# Spring2020.net
KiCad netlist of a schematic drawn in EAGLE
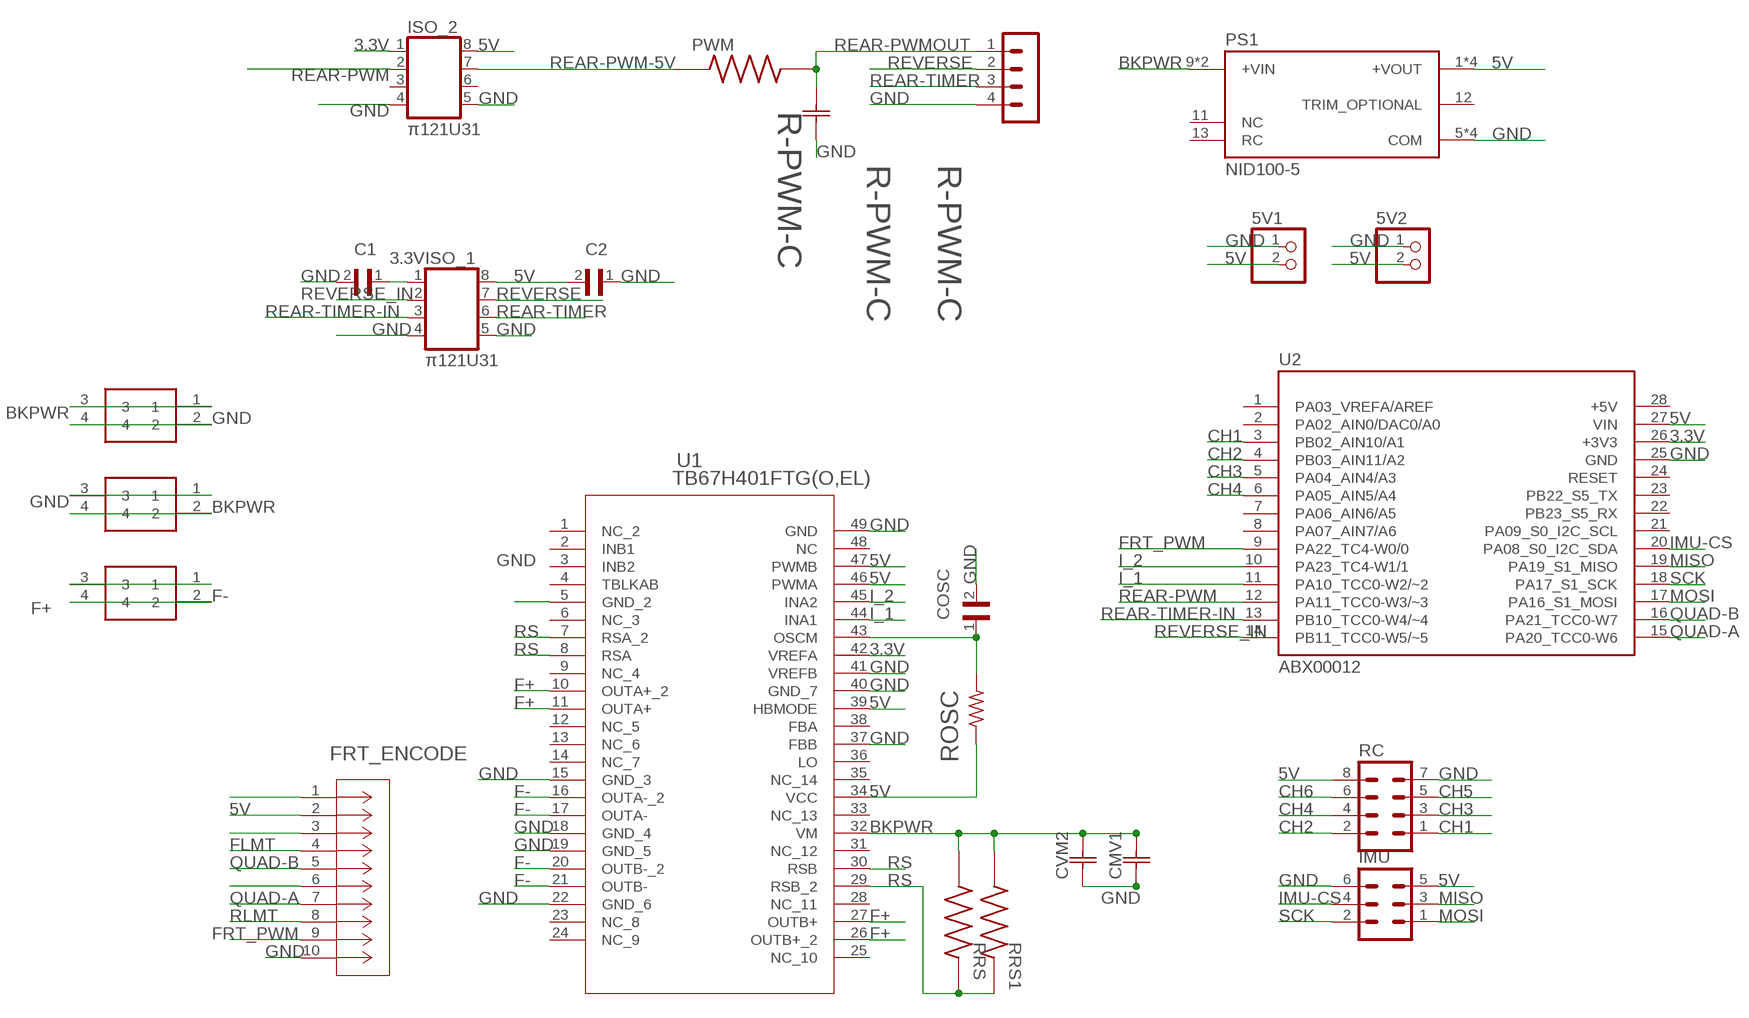
[diagram p0: schematic, sheet 1]

(export (version "E")
  (design (tool "Eeschema 10.0.6"))
  (components
    (comp (ref "5V1")
      (value "PINHD-1X2")
      (footprint "eagle-import:1X02")
      (libsource (lib "eagle-import") (part "PINHD-1X2"))
    )
    (comp (ref "5V2")
      (value "PINHD-1X2")
      (footprint "eagle-import:1X02")
      (libsource (lib "eagle-import") (part "PINHD-1X2"))
    )
    (comp (ref "C1")
      (value "CL05A105KP5NNNC")
      (footprint "eagle-import:CAPC1005X55N")
      (libsource (lib "eagle-import") (part "CL05A105KP5NNNC"))
    )
    (comp (ref "C2")
      (value "CL05A105KP5NNNC")
      (footprint "eagle-import:CAPC1005X55N")
      (libsource (lib "eagle-import") (part "CL05A105KP5NNNC"))
    )
    (comp (ref "CMV1")
      (value "UVY1H102MHD")
      (footprint "eagle-import:CAP_12.5_X_25_NCH")
      (fields (field (name "COPYRIGHT") "Copyright (C) 2022 Ultra Librarian. All rights reserved."))
      (libsource (lib "eagle-import") (part "UVY1H102MHD"))
    )
    (comp (ref "COSC")
      (value "GRM022R71A271KA01L")
      (footprint "eagle-import:CAPC0402X22N")
      (libsource (lib "eagle-import") (part "GRM022R71A271KA01L"))
    )
    (comp (ref "CVM2")
      (value "CL05B104KB54PNC")
      (footprint "eagle-import:CAP_CL_05_SAM")
      (fields (field (name "COPYRIGHT") "Copyright (C) 2022 Ultra Librarian. All rights reserved."))
      (libsource (lib "eagle-import") (part "CL05B104KB54PNC"))
    )
    (comp (ref "FRT_ENCODE")
      (value "3220-10-0100-00")
      (footprint "eagle-import:CONN_3220-10-0100-00_CNC")
      (fields (field (name "COPYRIGHT") "Copyright (C) 2022 Ultra Librarian. All rights reserved."))
      (libsource (lib "eagle-import") (part "3220-10-0100-00"))
    )
    (comp (ref "FRT_MTR")
      (value "2060-452_998-404")
      (footprint "eagle-import:2060452998404")
      (fields (field (name "MANUFACTURER_PART_NUMBER") "2060-452/998-404"))
      (libsource (lib "eagle-import") (part "2060-452_998-404"))
    )
    (comp (ref "IMU")
      (value "MA03-2")
      (footprint "eagle-import:MA03-2")
      (libsource (lib "eagle-import") (part "MA03-2"))
    )
    (comp (ref "ISO_1")
      (value "π121U31")
      (footprint "eagle-import:SO08")
      (libsource (lib "eagle-import") (part "π121U31"))
    )
    (comp (ref "ISO_2")
      (value "π121U31")
      (footprint "eagle-import:SO08")
      (libsource (lib "eagle-import") (part "π121U31"))
    )
    (comp (ref "PS1")
      (value "NID100-5")
      (footprint "eagle-import:CONV_NID100-5")
      (fields (field (name "MANUFACTURER") "Meanwell"))
      (libsource (lib "eagle-import") (part "NID100-5"))
    )
    (comp (ref "PWM")
      (value "ERJ1GNF6802C")
      (footprint "eagle-import:RES_ERJ1GNF6802C")
      (fields (field (name "MANUFACTURER") "Panasonic"))
      (libsource (lib "eagle-import") (part "ERJ1GNF6802C"))
    )
    (comp (ref "PWR_IN")
      (value "2060-452_998-404")
      (footprint "eagle-import:2060452998404")
      (fields (field (name "MANUFACTURER_PART_NUMBER") "2060-452/998-404"))
      (libsource (lib "eagle-import") (part "2060-452_998-404"))
    )
    (comp (ref "R-PWM-C")
      (value "CL03A105MQ3CSNC")
      (footprint "eagle-import:CAP_CL03_SAM")
      (fields (field (name "COPYRIGHT") "Copyright (C) 2022 Ultra Librarian. All rights reserved."))
      (libsource (lib "eagle-import") (part "CL03A105MQ3CSNC"))
    )
    (comp (ref "RC")
      (value "MA04-2")
      (footprint "eagle-import:MA04-2")
      (libsource (lib "eagle-import") (part "MA04-2"))
    )
    (comp (ref "REAR-MOTOR")
      (value "MA04-1")
      (footprint "eagle-import:MA04-1")
      (libsource (lib "eagle-import") (part "MA04-1"))
    )
    (comp (ref "REAR_PWR")
      (value "2060-452_998-404")
      (footprint "eagle-import:2060452998404")
      (fields (field (name "MANUFACTURER_PART_NUMBER") "2060-452/998-404"))
      (libsource (lib "eagle-import") (part "2060-452_998-404"))
    )
    (comp (ref "ROSC")
      (value "R-US_R0402")
      (footprint "eagle-import:R0402")
      (libsource (lib "eagle-import") (part "R-US_R0402"))
    )
    (comp (ref "RRS")
      (value "RLP73K3AR22FTDF")
      (footprint "eagle-import:RESC6331X70N")
      (libsource (lib "eagle-import") (part "RLP73K3AR22FTDF"))
    )
    (comp (ref "RRS1")
      (value "RLP73K3AR22FTDF")
      (footprint "eagle-import:RESC6331X70N")
      (libsource (lib "eagle-import") (part "RLP73K3AR22FTDF"))
    )
    (comp (ref "U1")
      (value "TB67H401FTG(O,EL)")
      (footprint "eagle-import:P-VQFN48-0707-0P50-004_TOS")
      (fields (field (name "COPYRIGHT") "Copyright (C) 2022 Ultra Librarian. All rights reserved."))
      (libsource (lib "eagle-import") (part "TB67H401FTG(O,EL)"))
    )
    (comp (ref "U2")
      (value "ABX00012")
      (footprint "eagle-import:ARDUINO_ABX00012")
      (fields (field (name "MANUFACTURER") "Arduino"))
      (libsource (lib "eagle-import") (part "ABX00012"))
    )
  )
  (nets
    (net (code "1") (name "/+5V") (class "Default")
      (node (ref "U2") (pin "28") (pinfunction "+5V_28") (pintype "power_in"))
    )
    (net (code "2") (name "/3.3V") (class "Default")
      (node (ref "C1") (pin "1") (pinfunction "1_1") (pintype "passive"))
      (node (ref "ISO_1") (pin "1") (pinfunction "1_1") (pintype "passive"))
      (node (ref "ISO_2") (pin "1") (pinfunction "1_1") (pintype "passive"))
      (node (ref "U1") (pin "42") (pinfunction "VREFA_42") (pintype "power_in"))
      (node (ref "U2") (pin "26") (pinfunction "+3V3_26") (pintype "power_in"))
    )
    (net (code "3") (name "/5V") (class "Default")
      (node (ref "5V1") (pin "2") (pinfunction "2_2") (pintype "passive"))
      (node (ref "5V2") (pin "2") (pinfunction "2_2") (pintype "passive"))
      (node (ref "C2") (pin "2") (pinfunction "2_2") (pintype "passive"))
      (node (ref "FRT_ENCODE") (pin "2") (pinfunction "2_2") (pintype "passive"))
      (node (ref "IMU") (pin "5") (pinfunction "5_5") (pintype "passive"))
      (node (ref "ISO_1") (pin "8") (pinfunction "8_8") (pintype "passive"))
      (node (ref "ISO_2") (pin "8") (pinfunction "8_8") (pintype "passive"))
      (node (ref "PS1") (pin "1") (pinfunction "+VOUT_1") (pintype "output"))
      (node (ref "PS1") (pin "2") (pinfunction "+VOUT_2") (pintype "output"))
      (node (ref "PS1") (pin "3") (pinfunction "+VOUT_3") (pintype "output"))
      (node (ref "PS1") (pin "4") (pinfunction "+VOUT_4") (pintype "output"))
      (node (ref "RC") (pin "8") (pinfunction "8_8") (pintype "passive"))
      (node (ref "ROSC") (pin "1") (pinfunction "1_1") (pintype "passive"))
      (node (ref "U1") (pin "34") (pinfunction "VCC_34") (pintype "power_in"))
      (node (ref "U1") (pin "39") (pinfunction "HBMODE_39") (pintype "passive"))
      (node (ref "U1") (pin "46") (pinfunction "PWMA_46") (pintype "passive"))
      (node (ref "U1") (pin "47") (pinfunction "PWMB_47") (pintype "passive"))
      (node (ref "U2") (pin "27") (pinfunction "VIN_27") (pintype "power_in"))
    )
    (net (code "4") (name "/BKPWR") (class "Default")
      (node (ref "CMV1") (pin "2") (pinfunction "2_2") (pintype "passive"))
      (node (ref "CVM2") (pin "2") (pinfunction "2_2") (pintype "passive"))
      (node (ref "PS1") (pin "10") (pinfunction "+VIN_10") (pintype "input"))
      (node (ref "PS1") (pin "9") (pinfunction "+VIN_9") (pintype "input"))
      (node (ref "PWR_IN") (pin "1") (pinfunction "1_1") (pintype "bidirectional"))
      (node (ref "PWR_IN") (pin "3") (pinfunction "3_3") (pintype "bidirectional"))
      (node (ref "REAR_PWR") (pin "2") (pinfunction "2_2") (pintype "bidirectional"))
      (node (ref "REAR_PWR") (pin "4") (pinfunction "4_4") (pintype "bidirectional"))
      (node (ref "RRS") (pin "1") (pinfunction "1_1") (pintype "passive"))
      (node (ref "RRS1") (pin "1") (pinfunction "1_1") (pintype "passive"))
      (node (ref "U1") (pin "32") (pinfunction "VM_32") (pintype "passive"))
    )
    (net (code "5") (name "/CH1") (class "Default")
      (node (ref "RC") (pin "1") (pinfunction "1_1") (pintype "passive"))
      (node (ref "U2") (pin "3") (pinfunction "PB02_AIN10/A1_3") (pintype "bidirectional"))
    )
    (net (code "6") (name "/CH2") (class "Default")
      (node (ref "RC") (pin "2") (pinfunction "2_2") (pintype "passive"))
      (node (ref "U2") (pin "4") (pinfunction "PB03_AIN11/A2_4") (pintype "bidirectional"))
    )
    (net (code "7") (name "/CH3") (class "Default")
      (node (ref "RC") (pin "3") (pinfunction "3_3") (pintype "passive"))
      (node (ref "U2") (pin "5") (pinfunction "PA04_AIN4/A3_5") (pintype "bidirectional"))
    )
    (net (code "8") (name "/CH4") (class "Default")
      (node (ref "RC") (pin "4") (pinfunction "4_4") (pintype "passive"))
      (node (ref "U2") (pin "6") (pinfunction "PA05_AIN5/A4_6") (pintype "bidirectional"))
    )
    (net (code "9") (name "/CH5") (class "Default")
      (node (ref "RC") (pin "5") (pinfunction "5_5") (pintype "passive"))
    )
    (net (code "10") (name "/CH6") (class "Default")
      (node (ref "RC") (pin "6") (pinfunction "6_6") (pintype "passive"))
    )
    (net (code "11") (name "/F+") (class "Default")
      (node (ref "FRT_MTR") (pin "2") (pinfunction "2_2") (pintype "bidirectional"))
      (node (ref "FRT_MTR") (pin "4") (pinfunction "4_4") (pintype "bidirectional"))
      (node (ref "U1") (pin "10") (pinfunction "OUTA+_2_10") (pintype "output"))
      (node (ref "U1") (pin "11") (pinfunction "OUTA+_11") (pintype "output"))
      (node (ref "U1") (pin "26") (pinfunction "OUTB+_2_26") (pintype "output"))
      (node (ref "U1") (pin "27") (pinfunction "OUTB+_27") (pintype "output"))
    )
    (net (code "12") (name "/F-") (class "Default")
      (node (ref "FRT_MTR") (pin "1") (pinfunction "1_1") (pintype "bidirectional"))
      (node (ref "FRT_MTR") (pin "3") (pinfunction "3_3") (pintype "bidirectional"))
      (node (ref "U1") (pin "16") (pinfunction "OUTA-_2_16") (pintype "output"))
      (node (ref "U1") (pin "17") (pinfunction "OUTA-_17") (pintype "output"))
      (node (ref "U1") (pin "20") (pinfunction "OUTB-_2_20") (pintype "output"))
      (node (ref "U1") (pin "21") (pinfunction "OUTB-_21") (pintype "output"))
    )
    (net (code "13") (name "/FLMT") (class "Default")
      (node (ref "FRT_ENCODE") (pin "4") (pinfunction "4_4") (pintype "passive"))
    )
    (net (code "14") (name "/FRT_PWM") (class "Default")
      (node (ref "FRT_ENCODE") (pin "9") (pinfunction "9_9") (pintype "passive"))
      (node (ref "U2") (pin "9") (pinfunction "PA22_TC4-W0/0_9") (pintype "bidirectional"))
    )
    (net (code "15") (name "/GND") (class "Default")
      (node (ref "5V1") (pin "1") (pinfunction "1_1") (pintype "passive"))
      (node (ref "5V2") (pin "1") (pinfunction "1_1") (pintype "passive"))
      (node (ref "C1") (pin "2") (pinfunction "2_2") (pintype "passive"))
      (node (ref "C2") (pin "1") (pinfunction "1_1") (pintype "passive"))
      (node (ref "CMV1") (pin "1") (pinfunction "1_1") (pintype "passive"))
      (node (ref "COSC") (pin "2") (pinfunction "2_2") (pintype "passive"))
      (node (ref "CVM2") (pin "1") (pinfunction "1_1") (pintype "passive"))
      (node (ref "FRT_ENCODE") (pin "10") (pinfunction "10_10") (pintype "passive"))
      (node (ref "IMU") (pin "6") (pinfunction "6_6") (pintype "passive"))
      (node (ref "ISO_1") (pin "4") (pinfunction "4_4") (pintype "passive"))
      (node (ref "ISO_1") (pin "5") (pinfunction "5_5") (pintype "passive"))
      (node (ref "ISO_2") (pin "4") (pinfunction "4_4") (pintype "passive"))
      (node (ref "ISO_2") (pin "5") (pinfunction "5_5") (pintype "passive"))
      (node (ref "PS1") (pin "5") (pinfunction "COM_5") (pintype "passive"))
      (node (ref "PS1") (pin "6") (pinfunction "COM_6") (pintype "passive"))
      (node (ref "PS1") (pin "7") (pinfunction "COM_7") (pintype "passive"))
      (node (ref "PS1") (pin "8") (pinfunction "COM_8") (pintype "passive"))
      (node (ref "PWR_IN") (pin "2") (pinfunction "2_2") (pintype "bidirectional"))
      (node (ref "PWR_IN") (pin "4") (pinfunction "4_4") (pintype "bidirectional"))
      (node (ref "R-PWM-C") (pin "2") (pinfunction "2_2") (pintype "passive"))
      (node (ref "RC") (pin "7") (pinfunction "7_7") (pintype "passive"))
      (node (ref "REAR-MOTOR") (pin "4") (pinfunction "4_4") (pintype "passive"))
      (node (ref "REAR_PWR") (pin "1") (pinfunction "1_1") (pintype "bidirectional"))
      (node (ref "REAR_PWR") (pin "3") (pinfunction "3_3") (pintype "bidirectional"))
      (node (ref "U1") (pin "15") (pinfunction "GND_3_15") (pintype "passive"))
      (node (ref "U1") (pin "18") (pinfunction "GND_4_18") (pintype "passive"))
      (node (ref "U1") (pin "19") (pinfunction "GND_5_19") (pintype "passive"))
      (node (ref "U1") (pin "22") (pinfunction "GND_6_22") (pintype "passive"))
      (node (ref "U1") (pin "37") (pinfunction "FBB_37") (pintype "passive"))
      (node (ref "U1") (pin "40") (pinfunction "GND_7_40") (pintype "passive"))
      (node (ref "U1") (pin "41") (pinfunction "VREFB_41") (pintype "power_in"))
      (node (ref "U1") (pin "49") (pinfunction "GND_49") (pintype "passive"))
      (node (ref "U1") (pin "5") (pinfunction "GND_2_5") (pintype "passive"))
      (node (ref "U2") (pin "25") (pinfunction "GND_25") (pintype "power_in"))
    )
    (net (code "16") (name "/IMU-CS") (class "Default")
      (node (ref "IMU") (pin "4") (pinfunction "4_4") (pintype "passive"))
      (node (ref "U2") (pin "20") (pinfunction "PA08_S0_I2C_SDA_20") (pintype "bidirectional"))
    )
    (net (code "17") (name "/I_1") (class "Default")
      (node (ref "U1") (pin "44") (pinfunction "INA1_44") (pintype "input"))
      (node (ref "U2") (pin "11") (pinfunction "PA10_TCC0-W2/~{2}_11") (pintype "bidirectional"))
    )
    (net (code "18") (name "/I_2") (class "Default")
      (node (ref "U1") (pin "45") (pinfunction "INA2_45") (pintype "input"))
      (node (ref "U2") (pin "10") (pinfunction "PA23_TC4-W1/1_10") (pintype "bidirectional"))
    )
    (net (code "19") (name "/MISO") (class "Default")
      (node (ref "IMU") (pin "3") (pinfunction "3_3") (pintype "passive"))
      (node (ref "U2") (pin "19") (pinfunction "PA19_S1_MISO_19") (pintype "bidirectional"))
    )
    (net (code "20") (name "/MOSI") (class "Default")
      (node (ref "IMU") (pin "1") (pinfunction "1_1") (pintype "passive"))
      (node (ref "U2") (pin "17") (pinfunction "PA16_S1_MOSI_17") (pintype "bidirectional"))
    )
    (net (code "21") (name "/QUAD-A") (class "Default")
      (node (ref "FRT_ENCODE") (pin "7") (pinfunction "7_7") (pintype "passive"))
      (node (ref "U2") (pin "15") (pinfunction "PA20_TCC0-W6_15") (pintype "bidirectional"))
    )
    (net (code "22") (name "/QUAD-B") (class "Default")
      (node (ref "FRT_ENCODE") (pin "5") (pinfunction "5_5") (pintype "passive"))
      (node (ref "U2") (pin "16") (pinfunction "PA21_TCC0-W7_16") (pintype "bidirectional"))
    )
    (net (code "23") (name "/REAR-PWM") (class "Default")
      (node (ref "ISO_2") (pin "2") (pinfunction "2_2") (pintype "passive"))
      (node (ref "U2") (pin "12") (pinfunction "PA11_TCC0-W3/~{3}_12") (pintype "bidirectional"))
    )
    (net (code "24") (name "/REAR-PWM-5V") (class "Default")
      (node (ref "ISO_2") (pin "7") (pinfunction "7_7") (pintype "passive"))
      (node (ref "PWM") (pin "1") (pinfunction "1_1") (pintype "passive"))
    )
    (net (code "25") (name "/REAR-PWMOUT") (class "Default")
      (node (ref "PWM") (pin "2") (pinfunction "2_2") (pintype "passive"))
      (node (ref "R-PWM-C") (pin "1") (pinfunction "1_1") (pintype "passive"))
      (node (ref "REAR-MOTOR") (pin "1") (pinfunction "1_1") (pintype "passive"))
    )
    (net (code "26") (name "/REAR-TIMER") (class "Default")
      (node (ref "ISO_1") (pin "6") (pinfunction "6_6") (pintype "passive"))
      (node (ref "REAR-MOTOR") (pin "3") (pinfunction "3_3") (pintype "passive"))
    )
    (net (code "27") (name "/REAR-TIMER-IN") (class "Default")
      (node (ref "ISO_1") (pin "3") (pinfunction "3_3") (pintype "passive"))
      (node (ref "U2") (pin "13") (pinfunction "PB10_TCC0-W4/~{4}_13") (pintype "bidirectional"))
    )
    (net (code "28") (name "/REVERSE") (class "Default")
      (node (ref "ISO_1") (pin "7") (pinfunction "7_7") (pintype "passive"))
      (node (ref "REAR-MOTOR") (pin "2") (pinfunction "2_2") (pintype "passive"))
    )
    (net (code "29") (name "/REVERSE_IN") (class "Default")
      (node (ref "ISO_1") (pin "2") (pinfunction "2_2") (pintype "passive"))
      (node (ref "U2") (pin "14") (pinfunction "PB11_TCC0-W5/~{5}_14") (pintype "bidirectional"))
    )
    (net (code "30") (name "/RLMT") (class "Default")
      (node (ref "FRT_ENCODE") (pin "8") (pinfunction "8_8") (pintype "passive"))
    )
    (net (code "31") (name "/RS") (class "Default")
      (node (ref "RRS") (pin "2") (pinfunction "2_2") (pintype "passive"))
      (node (ref "RRS1") (pin "2") (pinfunction "2_2") (pintype "passive"))
      (node (ref "U1") (pin "29") (pinfunction "RSB_2_29") (pintype "passive"))
      (node (ref "U1") (pin "30") (pinfunction "RSB_30") (pintype "passive"))
      (node (ref "U1") (pin "7") (pinfunction "RSA_2_7") (pintype "passive"))
      (node (ref "U1") (pin "8") (pinfunction "RSA_8") (pintype "passive"))
    )
    (net (code "32") (name "/SCK") (class "Default")
      (node (ref "IMU") (pin "2") (pinfunction "2_2") (pintype "passive"))
      (node (ref "U2") (pin "18") (pinfunction "PA17_S1_SCK_18") (pintype "bidirectional"))
    )
    (net (code "33") (name "Net-(U1-OSCM)") (class "Default")
      (node (ref "COSC") (pin "1") (pinfunction "1_1") (pintype "passive"))
      (node (ref "ROSC") (pin "2") (pinfunction "2_2") (pintype "passive"))
      (node (ref "U1") (pin "43") (pinfunction "OSCM_43") (pintype "passive"))
    )
    (net (code "34") (name "unconnected-(FRT_ENCODE-Pad1)") (class "Default")
      (node (ref "FRT_ENCODE") (pin "1") (pinfunction "1_1") (pintype "passive"))
    )
    (net (code "35") (name "unconnected-(FRT_ENCODE-Pad3)") (class "Default")
      (node (ref "FRT_ENCODE") (pin "3") (pinfunction "3_3") (pintype "passive"))
    )
    (net (code "36") (name "unconnected-(FRT_ENCODE-Pad6)") (class "Default")
      (node (ref "FRT_ENCODE") (pin "6") (pinfunction "6_6") (pintype "passive"))
    )
    (net (code "37") (name "unconnected-(ISO_2-Pad3)") (class "Default")
      (node (ref "ISO_2") (pin "3") (pinfunction "3_3") (pintype "passive"))
    )
    (net (code "38") (name "unconnected-(ISO_2-Pad6)") (class "Default")
      (node (ref "ISO_2") (pin "6") (pinfunction "6_6") (pintype "passive"))
    )
    (net (code "39") (name "unconnected-(PS1-NC-Pad11)") (class "Default")
      (node (ref "PS1") (pin "11") (pinfunction "NC_11") (pintype "no_connect"))
    )
    (net (code "40") (name "unconnected-(PS1-RC-Pad13)") (class "Default")
      (node (ref "PS1") (pin "13") (pinfunction "RC_13") (pintype "passive"))
    )
    (net (code "41") (name "unconnected-(PS1-TRIM_OPTIONAL-Pad12)") (class "Default")
      (node (ref "PS1") (pin "12") (pinfunction "TRIM_OPTIONAL_12") (pintype "passive"))
    )
    (net (code "42") (name "unconnected-(U1-FBA-Pad38)") (class "Default")
      (node (ref "U1") (pin "38") (pinfunction "FBA_38") (pintype "passive"))
    )
    (net (code "43") (name "unconnected-(U1-INB1-Pad2)") (class "Default")
      (node (ref "U1") (pin "2") (pinfunction "INB1_2") (pintype "input"))
    )
    (net (code "44") (name "unconnected-(U1-INB2-Pad3)") (class "Default")
      (node (ref "U1") (pin "3") (pinfunction "INB2_3") (pintype "input"))
    )
    (net (code "45") (name "unconnected-(U1-LO-Pad36)") (class "Default")
      (node (ref "U1") (pin "36") (pinfunction "LO_36") (pintype "passive"))
    )
    (net (code "46") (name "unconnected-(U1-NC-Pad48)") (class "Default")
      (node (ref "U1") (pin "48") (pinfunction "NC_48") (pintype "no_connect"))
    )
    (net (code "47") (name "unconnected-(U1-NC_2-Pad1)") (class "Default")
      (node (ref "U1") (pin "1") (pinfunction "NC_2_1") (pintype "no_connect"))
    )
    (net (code "48") (name "unconnected-(U1-NC_3-Pad6)") (class "Default")
      (node (ref "U1") (pin "6") (pinfunction "NC_3_6") (pintype "no_connect"))
    )
    (net (code "49") (name "unconnected-(U1-NC_4-Pad9)") (class "Default")
      (node (ref "U1") (pin "9") (pinfunction "NC_4_9") (pintype "no_connect"))
    )
    (net (code "50") (name "unconnected-(U1-NC_5-Pad12)") (class "Default")
      (node (ref "U1") (pin "12") (pinfunction "NC_5_12") (pintype "no_connect"))
    )
    (net (code "51") (name "unconnected-(U1-NC_6-Pad13)") (class "Default")
      (node (ref "U1") (pin "13") (pinfunction "NC_6_13") (pintype "no_connect"))
    )
    (net (code "52") (name "unconnected-(U1-NC_7-Pad14)") (class "Default")
      (node (ref "U1") (pin "14") (pinfunction "NC_7_14") (pintype "no_connect"))
    )
    (net (code "53") (name "unconnected-(U1-NC_8-Pad23)") (class "Default")
      (node (ref "U1") (pin "23") (pinfunction "NC_8_23") (pintype "no_connect"))
    )
    (net (code "54") (name "unconnected-(U1-NC_9-Pad24)") (class "Default")
      (node (ref "U1") (pin "24") (pinfunction "NC_9_24") (pintype "no_connect"))
    )
    (net (code "55") (name "unconnected-(U1-NC_10-Pad25)") (class "Default")
      (node (ref "U1") (pin "25") (pinfunction "NC_10_25") (pintype "no_connect"))
    )
    (net (code "56") (name "unconnected-(U1-NC_11-Pad28)") (class "Default")
      (node (ref "U1") (pin "28") (pinfunction "NC_11_28") (pintype "no_connect"))
    )
    (net (code "57") (name "unconnected-(U1-NC_12-Pad31)") (class "Default")
      (node (ref "U1") (pin "31") (pinfunction "NC_12_31") (pintype "no_connect"))
    )
    (net (code "58") (name "unconnected-(U1-NC_13-Pad33)") (class "Default")
      (node (ref "U1") (pin "33") (pinfunction "NC_13_33") (pintype "no_connect"))
    )
    (net (code "59") (name "unconnected-(U1-NC_14-Pad35)") (class "Default")
      (node (ref "U1") (pin "35") (pinfunction "NC_14_35") (pintype "no_connect"))
    )
    (net (code "60") (name "unconnected-(U1-TBLKAB-Pad4)") (class "Default")
      (node (ref "U1") (pin "4") (pinfunction "TBLKAB_4") (pintype "passive"))
    )
    (net (code "61") (name "unconnected-(U2-PA02_AIN0{slash}DAC0{slash}A0-Pad2)") (class "Default")
      (node (ref "U2") (pin "2") (pinfunction "PA02_AIN0/DAC0/A0_2") (pintype "bidirectional"))
    )
    (net (code "62") (name "unconnected-(U2-PA03_VREFA{slash}AREF-Pad1)") (class "Default")
      (node (ref "U2") (pin "1") (pinfunction "PA03_VREFA/AREF_1") (pintype "bidirectional"))
    )
    (net (code "63") (name "unconnected-(U2-PA06_AIN6{slash}A5-Pad7)") (class "Default")
      (node (ref "U2") (pin "7") (pinfunction "PA06_AIN6/A5_7") (pintype "bidirectional"))
    )
    (net (code "64") (name "unconnected-(U2-PA07_AIN7{slash}A6-Pad8)") (class "Default")
      (node (ref "U2") (pin "8") (pinfunction "PA07_AIN7/A6_8") (pintype "bidirectional"))
    )
    (net (code "65") (name "unconnected-(U2-PA09_S0_I2C_SCL-Pad21)") (class "Default")
      (node (ref "U2") (pin "21") (pinfunction "PA09_S0_I2C_SCL_21") (pintype "bidirectional"))
    )
    (net (code "66") (name "unconnected-(U2-PB22_S5_TX-Pad23)") (class "Default")
      (node (ref "U2") (pin "23") (pinfunction "PB22_S5_TX_23") (pintype "bidirectional"))
    )
    (net (code "67") (name "unconnected-(U2-PB23_S5_RX-Pad22)") (class "Default")
      (node (ref "U2") (pin "22") (pinfunction "PB23_S5_RX_22") (pintype "bidirectional"))
    )
    (net (code "68") (name "unconnected-(U2-RESET-Pad24)") (class "Default")
      (node (ref "U2") (pin "24") (pinfunction "RESET_24") (pintype "input"))
    )
  )
)
